# Gaussmeter_ver2.net
KiCad netlist of a schematic drawn in EAGLE
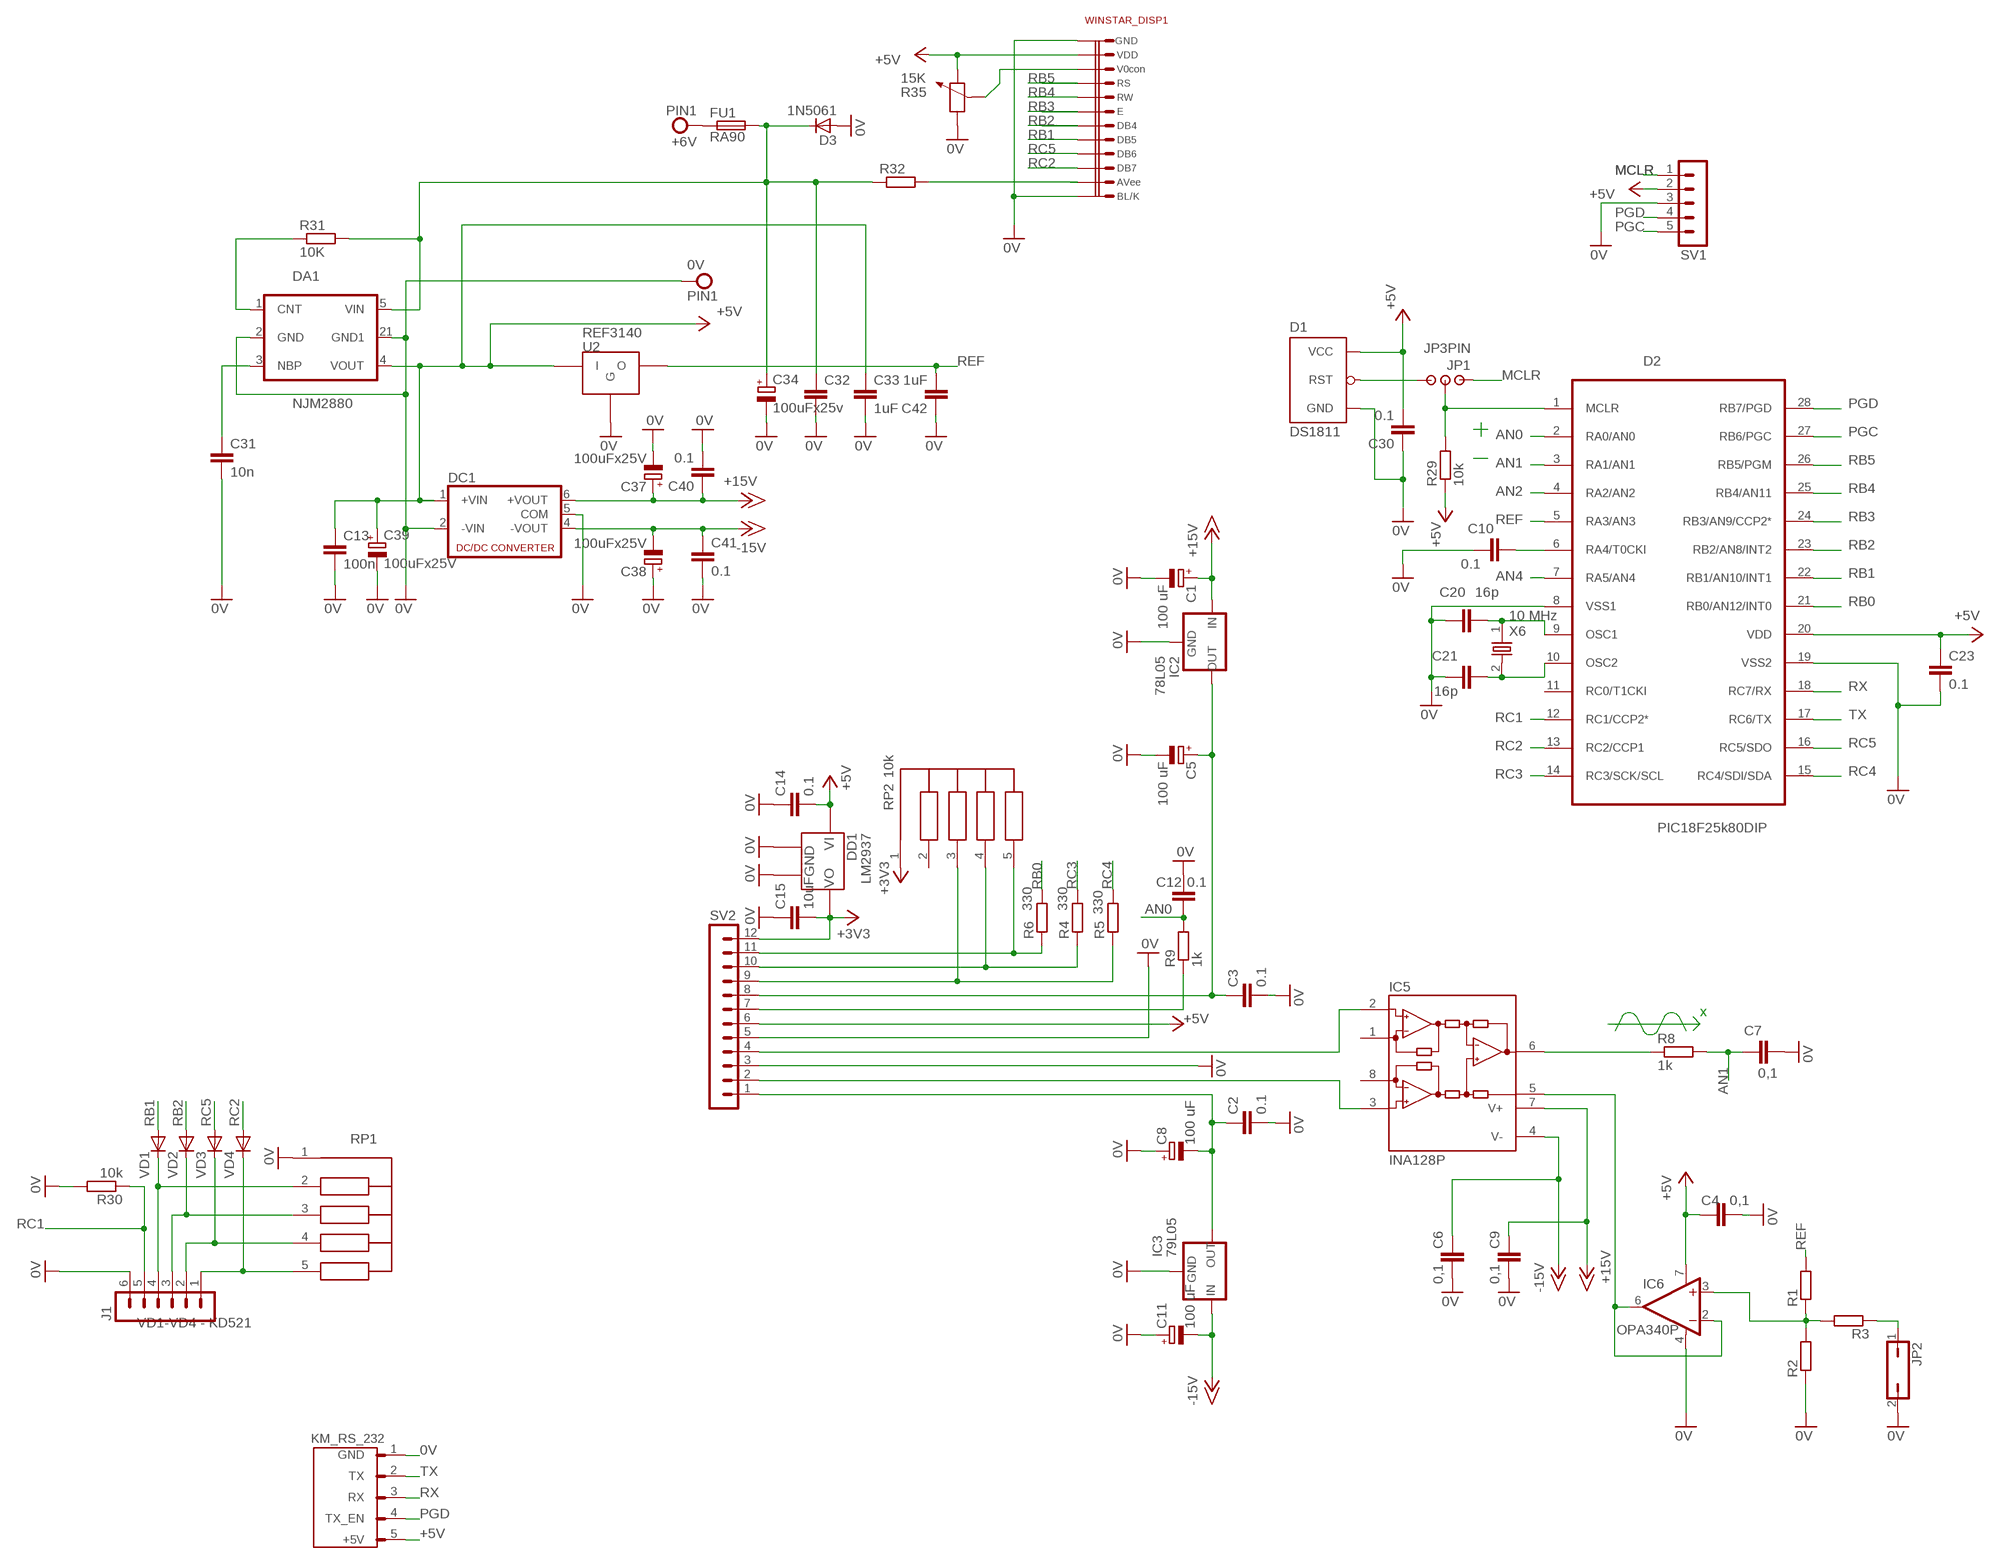
[diagram p0: schematic, sheet 1]

(export (version "E")
  (design (tool "Eeschema 10.0.6"))
  (components
    (comp (ref "+6V")
      (value "PIN1")
      (footprint "eagle-import:PIN1")
      (libsource (lib "eagle-import") (part "PIN1"))
    )
    (comp (ref "0V")
      (value "PIN1")
      (footprint "eagle-import:PIN1")
      (libsource (lib "eagle-import") (part "PIN1"))
    )
    (comp (ref "C1")
      (value "100 uF")
      (footprint "eagle-import:E2,5-6")
      (libsource (lib "eagle-import") (part "CPOL-EUE2.5-6"))
    )
    (comp (ref "C2")
      (value "0.1")
      (footprint "eagle-import:C0805")
      (libsource (lib "eagle-import") (part "C-EUC0805"))
    )
    (comp (ref "C3")
      (value "0.1")
      (footprint "eagle-import:C0805")
      (libsource (lib "eagle-import") (part "C-EUC0805"))
    )
    (comp (ref "C4")
      (value "0,1")
      (footprint "eagle-import:C0805")
      (libsource (lib "eagle-import") (part "C-EUC0805"))
    )
    (comp (ref "C5")
      (value "100 uF")
      (footprint "eagle-import:E2,5-6")
      (libsource (lib "eagle-import") (part "CPOL-EUE2.5-6"))
    )
    (comp (ref "C6")
      (value "0,1")
      (footprint "eagle-import:C0805")
      (libsource (lib "eagle-import") (part "C-EUC0805"))
    )
    (comp (ref "C7")
      (value "0,1")
      (footprint "eagle-import:C0805")
      (libsource (lib "eagle-import") (part "C-EUC0805"))
    )
    (comp (ref "C8")
      (value "100 uF")
      (footprint "eagle-import:E2,5-6")
      (libsource (lib "eagle-import") (part "CPOL-EUE2.5-6"))
    )
    (comp (ref "C9")
      (value "0,1")
      (footprint "eagle-import:C0805")
      (libsource (lib "eagle-import") (part "C-EUC0805"))
    )
    (comp (ref "C10")
      (value "0.1")
      (footprint "eagle-import:C0805D")
      (libsource (lib "eagle-import") (part "C0805"))
    )
    (comp (ref "C11")
      (value "100 uF")
      (footprint "eagle-import:E2,5-6")
      (libsource (lib "eagle-import") (part "CPOL-EUE2.5-6"))
    )
    (comp (ref "C12")
      (value "0.1")
      (footprint "eagle-import:C0805")
      (libsource (lib "eagle-import") (part "C-EUC0805"))
    )
    (comp (ref "C13")
      (value "100n")
      (footprint "eagle-import:C0805D")
      (libsource (lib "eagle-import") (part "C0805"))
    )
    (comp (ref "C14")
      (value "0.1")
      (footprint "eagle-import:C0805D")
      (libsource (lib "eagle-import") (part "C0805"))
    )
    (comp (ref "C15")
      (value "10uF")
      (footprint "eagle-import:C0805D")
      (libsource (lib "eagle-import") (part "C0805"))
    )
    (comp (ref "C20")
      (value "16p")
      (footprint "eagle-import:C0805D")
      (libsource (lib "eagle-import") (part "C0805"))
    )
    (comp (ref "C21")
      (value "16p")
      (footprint "eagle-import:C0805D")
      (libsource (lib "eagle-import") (part "C0805"))
    )
    (comp (ref "C23")
      (value "0.1")
      (footprint "eagle-import:C0805")
      (libsource (lib "eagle-import") (part "C-EUC0805"))
    )
    (comp (ref "C30")
      (value "0.1")
      (footprint "eagle-import:C0805D")
      (libsource (lib "eagle-import") (part "C0805"))
    )
    (comp (ref "C31")
      (value "10n")
      (footprint "eagle-import:C0805D")
      (libsource (lib "eagle-import") (part "C0805"))
    )
    (comp (ref "C32")
      (value "C0805")
      (footprint "eagle-import:C0805D")
      (libsource (lib "eagle-import") (part "C0805"))
    )
    (comp (ref "C33")
      (value "1uF")
      (footprint "eagle-import:C0805D")
      (libsource (lib "eagle-import") (part "C0805"))
    )
    (comp (ref "C34")
      (value "100uFx25v")
      (footprint "eagle-import:E2,5-6")
      (libsource (lib "eagle-import") (part "CPOL-EUE2.5-6"))
    )
    (comp (ref "C37")
      (value "100uFx25V")
      (footprint "eagle-import:E2,5-6")
      (libsource (lib "eagle-import") (part "CPOL-EUE2.5-6"))
    )
    (comp (ref "C38")
      (value "100uFx25V")
      (footprint "eagle-import:E2,5-6")
      (libsource (lib "eagle-import") (part "CPOL-EUE2.5-6"))
    )
    (comp (ref "C39")
      (value "100uFx25V")
      (footprint "eagle-import:E2,5-6")
      (libsource (lib "eagle-import") (part "CPOL-EUE2.5-6"))
    )
    (comp (ref "C40")
      (value "0.1")
      (footprint "eagle-import:C0805D")
      (libsource (lib "eagle-import") (part "C0805"))
    )
    (comp (ref "C41")
      (value "0.1")
      (footprint "eagle-import:C0805D")
      (libsource (lib "eagle-import") (part "C0805"))
    )
    (comp (ref "C42")
      (value "1uF")
      (footprint "eagle-import:C0805D")
      (libsource (lib "eagle-import") (part "C0805"))
    )
    (comp (ref "D1")
      (value "DS1811")
      (footprint "eagle-import:TO92-60")
      (libsource (lib "eagle-import") (part "DS1811"))
    )
    (comp (ref "D2")
      (value "PIC18F25k80DIP")
      (footprint "eagle-import:DIL28-3")
      (libsource (lib "eagle-import") (part "PIC18F2320DIP"))
    )
    (comp (ref "D3")
      (value "1N5061")
      (footprint "eagle-import:DO41-10")
      (libsource (lib "eagle-import") (part "1N5061"))
    )
    (comp (ref "DA1")
      (value "NJM2880")
      (footprint "eagle-import:SOT89-5")
      (libsource (lib "eagle-import") (part "NJM2880"))
    )
    (comp (ref "DC1")
      (value "NMA")
      (footprint "eagle-import:NMA")
      (fields (field (name "MF") "C & D TECHNOLOGIES, INC") (field (name "MPN") "NMA0515SC"))
      (libsource (lib "eagle-import") (part "NMA"))
    )
    (comp (ref "DD1")
      (value "LM2937")
      (footprint "eagle-import:SOT223")
      (libsource (lib "eagle-import") (part "LM2937"))
    )
    (comp (ref "FU1")
      (value "RA90")
      (footprint "eagle-import:RA90")
      (libsource (lib "eagle-import") (part "RA90"))
    )
    (comp (ref "IC2")
      (value "78L05")
      (footprint "eagle-import:78LXX")
      (libsource (lib "eagle-import") (part "78LXX"))
    )
    (comp (ref "IC3")
      (value "79L05")
      (footprint "eagle-import:79LXX")
      (libsource (lib "eagle-import") (part "79LXX"))
    )
    (comp (ref "IC5")
      (value "INA128P")
      (footprint "eagle-import:DIL08")
      (fields (field (name "MF") "TEXAS INSTRUMENTS"))
      (libsource (lib "eagle-import") (part "INA128P"))
    )
    (comp (ref "IC6")
      (value "OPA340P")
      (footprint "eagle-import:DIL08")
      (fields (field (name "MPN") "OPA340PA"))
      (libsource (lib "eagle-import") (part "OPA340P"))
    )
    (comp (ref "J1")
      (value "MA06-1")
      (footprint "eagle-import:MA06-1")
      (libsource (lib "eagle-import") (part "MA06-1"))
    )
    (comp (ref "JP1")
      (value "JP3PIN")
      (footprint "eagle-import:PLC-3PIN")
      (libsource (lib "eagle-import") (part "JP3PIN"))
    )
    (comp (ref "JP2")
      (value "JP1Q")
      (footprint "eagle-import:JP1")
      (libsource (lib "eagle-import") (part "JP1Q"))
    )
    (comp (ref "R1")
      (value "R-EU_R0805")
      (footprint "eagle-import:R0805")
      (libsource (lib "eagle-import") (part "R-EU_R0805"))
    )
    (comp (ref "R2")
      (value "R-EU_R0805")
      (footprint "eagle-import:R0805")
      (libsource (lib "eagle-import") (part "R-EU_R0805"))
    )
    (comp (ref "R3")
      (value "R-EU_R0805")
      (footprint "eagle-import:R0805")
      (libsource (lib "eagle-import") (part "R-EU_R0805"))
    )
    (comp (ref "R4")
      (value "330")
      (footprint "eagle-import:R0805")
      (libsource (lib "eagle-import") (part "R-EU_R0805"))
    )
    (comp (ref "R5")
      (value "330")
      (footprint "eagle-import:R0805")
      (libsource (lib "eagle-import") (part "R-EU_R0805"))
    )
    (comp (ref "R6")
      (value "330")
      (footprint "eagle-import:R0805")
      (libsource (lib "eagle-import") (part "R-EU_R0805"))
    )
    (comp (ref "R8")
      (value "1k")
      (footprint "eagle-import:R0805")
      (libsource (lib "eagle-import") (part "R-EU_R0805"))
    )
    (comp (ref "R9")
      (value "1k")
      (footprint "eagle-import:R0805")
      (libsource (lib "eagle-import") (part "R-EU_R0805"))
    )
    (comp (ref "R29")
      (value "10k")
      (footprint "eagle-import:R0805D")
      (libsource (lib "eagle-import") (part "R0805"))
    )
    (comp (ref "R30")
      (value "10k")
      (footprint "eagle-import:R0805D")
      (libsource (lib "eagle-import") (part "R0805"))
    )
    (comp (ref "R31")
      (value "10K")
      (footprint "eagle-import:R0805D")
      (libsource (lib "eagle-import") (part "R0805"))
    )
    (comp (ref "R32")
      (value "MLT025\"")
      (footprint "eagle-import:0207_10")
      (libsource (lib "eagle-import") (part "MLT025{dblquote}"))
    )
    (comp (ref "R35")
      (value "15K")
      (footprint "eagle-import:RTRIM3329H")
      (libsource (lib "eagle-import") (part "RTRIM3329H"))
    )
    (comp (ref "RP1")
      (value "NR1-4-4")
      (footprint "eagle-import:SIP5")
      (libsource (lib "eagle-import") (part "NR1-4-4"))
    )
    (comp (ref "RP2")
      (value "10k")
      (footprint "eagle-import:SIP5")
      (libsource (lib "eagle-import") (part "NR1-4-4"))
    )
    (comp (ref "SV1")
      (value "MA05-1")
      (footprint "eagle-import:MA05-1")
      (libsource (lib "eagle-import") (part "MA05-1"))
    )
    (comp (ref "SV2")
      (value "MA12-1")
      (footprint "eagle-import:MA12-1")
      (libsource (lib "eagle-import") (part "MA12-1"))
    )
    (comp (ref "U2")
      (value "REF3140")
      (footprint "eagle-import:SOT23-W")
      (libsource (lib "eagle-import") (part "REF3140"))
    )
    (comp (ref "VD1")
      (value "KD521")
      (footprint "eagle-import:DO35-10")
      (libsource (lib "eagle-import") (part "KD521"))
    )
    (comp (ref "VD2")
      (value "KD521")
      (footprint "eagle-import:DO35-10")
      (libsource (lib "eagle-import") (part "KD521"))
    )
    (comp (ref "VD3")
      (value "KD521")
      (footprint "eagle-import:DO35-10")
      (libsource (lib "eagle-import") (part "KD521"))
    )
    (comp (ref "VD4")
      (value "KD521")
      (footprint "eagle-import:DO35-10")
      (libsource (lib "eagle-import") (part "KD521"))
    )
    (comp (ref "WINSTAR_DISP1")
      (value "WINSTAR16X4DSPL_12")
      (footprint "eagle-import:WINSTAR16X4_12")
      (libsource (lib "eagle-import") (part "WINSTAR16X4DSPL_12"))
    )
    (comp (ref "X1")
      (value "KM_RS_232")
      (footprint "eagle-import:KM_RS_232")
      (libsource (lib "eagle-import") (part "KM_RS_232"))
    )
    (comp (ref "X6")
      (value "10 MHz")
      (footprint "eagle-import:HC49_S")
      (libsource (lib "eagle-import") (part "HC49/S"))
    )
  )
  (nets
    (net (code "1") (name "+3V3") (class "Default")
      (node (ref "C15") (pin "2") (pinfunction "2_2") (pintype "passive"))
      (node (ref "DD1") (pin "OUTPUT") (pinfunction "VO_OUTPUT") (pintype "power_in"))
      (node (ref "RP2") (pin "1") (pinfunction "P$1_1") (pintype "passive"))
      (node (ref "SV2") (pin "12") (pinfunction "12_12") (pintype "passive"))
    )
    (net (code "2") (name "+5V") (class "Default")
      (node (ref "C13") (pin "1") (pinfunction "1_1") (pintype "passive"))
      (node (ref "C14") (pin "2") (pinfunction "2_2") (pintype "passive"))
      (node (ref "C23") (pin "1") (pinfunction "1_1") (pintype "passive"))
      (node (ref "C30") (pin "2") (pinfunction "2_2") (pintype "passive"))
      (node (ref "C33") (pin "1") (pinfunction "1_1") (pintype "passive"))
      (node (ref "C39") (pin "+") (pinfunction "+_+") (pintype "passive"))
      (node (ref "C4") (pin "2") (pinfunction "2_2") (pintype "passive"))
      (node (ref "D1") (pin "2") (pinfunction "VCC_2") (pintype "power_in"))
      (node (ref "D2") (pin "20") (pinfunction "VDD_20") (pintype "bidirectional"))
      (node (ref "DA1") (pin "4") (pinfunction "VOUT_4") (pintype "bidirectional"))
      (node (ref "DC1") (pin "1") (pinfunction "+VIN_1") (pintype "passive"))
      (node (ref "DD1") (pin "INPUT") (pinfunction "VI_INPUT") (pintype "power_in"))
      (node (ref "IC6") (pin "7") (pinfunction "V+_7") (pintype "power_in"))
      (node (ref "R29") (pin "P$1") (pinfunction "1_P$1") (pintype "passive"))
      (node (ref "R35") (pin "2") (pinfunction "2_2") (pintype "passive"))
      (node (ref "SV1") (pin "2") (pinfunction "2_2") (pintype "passive"))
      (node (ref "SV2") (pin "6") (pinfunction "6_6") (pintype "passive"))
      (node (ref "U2") (pin "IN") (pinfunction "I_IN") (pintype "bidirectional"))
      (node (ref "WINSTAR_DISP1") (pin "P$2") (pinfunction "VDD_P$2") (pintype "bidirectional"))
      (node (ref "X1") (pin "5") (pinfunction "+5V_5") (pintype "bidirectional"))
    )
    (net (code "3") (name "+15V") (class "Default")
      (node (ref "C1") (pin "+") (pinfunction "+_+") (pintype "passive"))
      (node (ref "C37") (pin "+") (pinfunction "+_+") (pintype "passive"))
      (node (ref "C40") (pin "1") (pinfunction "1_1") (pintype "passive"))
      (node (ref "C9") (pin "1") (pinfunction "1_1") (pintype "passive"))
      (node (ref "DC1") (pin "6") (pinfunction "+VOUT_6") (pintype "passive"))
      (node (ref "IC2") (pin "IN") (pinfunction "IN_IN") (pintype "input"))
      (node (ref "IC5") (pin "7") (pinfunction "V+_7") (pintype "power_in"))
    )
    (net (code "4") (name "-15V") (class "Default")
      (node (ref "C11") (pin "-") (pinfunction "-_-") (pintype "passive"))
      (node (ref "C38") (pin "-") (pinfunction "-_-") (pintype "passive"))
      (node (ref "C41") (pin "1") (pinfunction "1_1") (pintype "passive"))
      (node (ref "C6") (pin "1") (pinfunction "1_1") (pintype "passive"))
      (node (ref "DC1") (pin "4") (pinfunction "-VOUT_4") (pintype "passive"))
      (node (ref "IC3") (pin "IN") (pinfunction "IN_IN") (pintype "input"))
      (node (ref "IC5") (pin "4") (pinfunction "V-_4") (pintype "power_in"))
    )
    (net (code "5") (name "/AN0") (class "Default")
      (node (ref "C12") (pin "1") (pinfunction "1_1") (pintype "passive"))
      (node (ref "D2") (pin "2") (pinfunction "RA0/AN0_2") (pintype "bidirectional"))
      (node (ref "R9") (pin "2") (pinfunction "2_2") (pintype "passive"))
    )
    (net (code "6") (name "/AN1") (class "Default")
      (node (ref "C7") (pin "1") (pinfunction "1_1") (pintype "passive"))
      (node (ref "D2") (pin "3") (pinfunction "RA1/AN1_3") (pintype "bidirectional"))
      (node (ref "R8") (pin "2") (pinfunction "2_2") (pintype "passive"))
    )
    (net (code "7") (name "/AN2") (class "Default")
      (node (ref "D2") (pin "4") (pinfunction "RA2/AN2_4") (pintype "bidirectional"))
    )
    (net (code "8") (name "/AN4") (class "Default")
      (node (ref "D2") (pin "7") (pinfunction "RA5/AN4_7") (pintype "bidirectional"))
    )
    (net (code "9") (name "/MCLR") (class "Default")
      (node (ref "JP1") (pin "P$1") (pinfunction "P$1_P$1") (pintype "bidirectional"))
      (node (ref "SV1") (pin "1") (pinfunction "1_1") (pintype "passive"))
    )
    (net (code "10") (name "/PGC") (class "Default")
      (node (ref "D2") (pin "27") (pinfunction "RB6/PGC_27") (pintype "bidirectional"))
      (node (ref "SV1") (pin "5") (pinfunction "5_5") (pintype "passive"))
    )
    (net (code "11") (name "/PGD") (class "Default")
      (node (ref "D2") (pin "28") (pinfunction "RB7/PGD_28") (pintype "bidirectional"))
      (node (ref "SV1") (pin "4") (pinfunction "4_4") (pintype "passive"))
      (node (ref "X1") (pin "4") (pinfunction "TX_EN_4") (pintype "bidirectional"))
    )
    (net (code "12") (name "/RB0") (class "Default")
      (node (ref "D2") (pin "21") (pinfunction "RB0/AN12/INT0_21") (pintype "bidirectional"))
      (node (ref "R6") (pin "2") (pinfunction "2_2") (pintype "passive"))
    )
    (net (code "13") (name "/RB1") (class "Default")
      (node (ref "D2") (pin "22") (pinfunction "RB1/AN10/INT1_22") (pintype "bidirectional"))
      (node (ref "VD1") (pin "A") (pinfunction "A_A") (pintype "passive"))
      (node (ref "WINSTAR_DISP1") (pin "P$8") (pinfunction "DB5_P$8") (pintype "bidirectional"))
    )
    (net (code "14") (name "/RB2") (class "Default")
      (node (ref "D2") (pin "23") (pinfunction "RB2/AN8/INT2_23") (pintype "bidirectional"))
      (node (ref "VD2") (pin "A") (pinfunction "A_A") (pintype "passive"))
      (node (ref "WINSTAR_DISP1") (pin "P$7") (pinfunction "DB4_P$7") (pintype "bidirectional"))
    )
    (net (code "15") (name "/RB3") (class "Default")
      (node (ref "D2") (pin "24") (pinfunction "RB3/AN9/CCP2*_24") (pintype "bidirectional"))
      (node (ref "WINSTAR_DISP1") (pin "P$6") (pinfunction "E_P$6") (pintype "bidirectional"))
    )
    (net (code "16") (name "/RB4") (class "Default")
      (node (ref "D2") (pin "25") (pinfunction "RB4/AN11_25") (pintype "bidirectional"))
      (node (ref "WINSTAR_DISP1") (pin "P$5") (pinfunction "RW_P$5") (pintype "bidirectional"))
    )
    (net (code "17") (name "/RB5") (class "Default")
      (node (ref "D2") (pin "26") (pinfunction "RB5/PGM_26") (pintype "bidirectional"))
      (node (ref "WINSTAR_DISP1") (pin "P$4") (pinfunction "RS_P$4") (pintype "bidirectional"))
    )
    (net (code "18") (name "/RC1") (class "Default")
      (node (ref "D2") (pin "12") (pinfunction "RC1/CCP2*_12") (pintype "bidirectional"))
      (node (ref "J1") (pin "5") (pinfunction "5_5") (pintype "passive"))
      (node (ref "R30") (pin "P$1") (pinfunction "1_P$1") (pintype "passive"))
    )
    (net (code "19") (name "/RC2") (class "Default")
      (node (ref "D2") (pin "13") (pinfunction "RC2/CCP1_13") (pintype "bidirectional"))
      (node (ref "VD4") (pin "A") (pinfunction "A_A") (pintype "passive"))
      (node (ref "WINSTAR_DISP1") (pin "P$10") (pinfunction "DB7_P$10") (pintype "bidirectional"))
    )
    (net (code "20") (name "/RC3") (class "Default")
      (node (ref "D2") (pin "14") (pinfunction "RC3/SCK/SCL_14") (pintype "bidirectional"))
      (node (ref "R4") (pin "2") (pinfunction "2_2") (pintype "passive"))
    )
    (net (code "21") (name "/RC4") (class "Default")
      (node (ref "D2") (pin "15") (pinfunction "RC4/SDI/SDA_15") (pintype "bidirectional"))
      (node (ref "R5") (pin "2") (pinfunction "2_2") (pintype "passive"))
    )
    (net (code "22") (name "/RC5") (class "Default")
      (node (ref "D2") (pin "16") (pinfunction "RC5/SDO_16") (pintype "bidirectional"))
      (node (ref "VD3") (pin "A") (pinfunction "A_A") (pintype "passive"))
      (node (ref "WINSTAR_DISP1") (pin "P$9") (pinfunction "DB6_P$9") (pintype "bidirectional"))
    )
    (net (code "23") (name "/REF") (class "Default")
      (node (ref "C42") (pin "2") (pinfunction "2_2") (pintype "passive"))
      (node (ref "D2") (pin "5") (pinfunction "RA3/AN3_5") (pintype "bidirectional"))
      (node (ref "R1") (pin "2") (pinfunction "2_2") (pintype "passive"))
      (node (ref "U2") (pin "OUT") (pinfunction "O_OUT") (pintype "bidirectional"))
    )
    (net (code "24") (name "/RX") (class "Default")
      (node (ref "D2") (pin "18") (pinfunction "RC7/RX_18") (pintype "bidirectional"))
      (node (ref "X1") (pin "3") (pinfunction "RX_3") (pintype "bidirectional"))
    )
    (net (code "25") (name "/TX") (class "Default")
      (node (ref "D2") (pin "17") (pinfunction "RC6/TX_17") (pintype "bidirectional"))
      (node (ref "X1") (pin "2") (pinfunction "TX_2") (pintype "bidirectional"))
    )
    (net (code "26") (name "0V") (class "Default")
      (node (ref "0V") (pin "P$1") (pinfunction "P$1_P$1") (pintype "passive"))
      (node (ref "C1") (pin "-") (pinfunction "-_-") (pintype "passive"))
      (node (ref "C10") (pin "2") (pinfunction "2_2") (pintype "passive"))
      (node (ref "C11") (pin "+") (pinfunction "+_+") (pintype "passive"))
      (node (ref "C12") (pin "2") (pinfunction "2_2") (pintype "passive"))
      (node (ref "C13") (pin "2") (pinfunction "2_2") (pintype "passive"))
      (node (ref "C14") (pin "1") (pinfunction "1_1") (pintype "passive"))
      (node (ref "C15") (pin "1") (pinfunction "1_1") (pintype "passive"))
      (node (ref "C2") (pin "2") (pinfunction "2_2") (pintype "passive"))
      (node (ref "C20") (pin "2") (pinfunction "2_2") (pintype "passive"))
      (node (ref "C21") (pin "1") (pinfunction "1_1") (pintype "passive"))
      (node (ref "C23") (pin "2") (pinfunction "2_2") (pintype "passive"))
      (node (ref "C3") (pin "2") (pinfunction "2_2") (pintype "passive"))
      (node (ref "C30") (pin "1") (pinfunction "1_1") (pintype "passive"))
      (node (ref "C31") (pin "2") (pinfunction "2_2") (pintype "passive"))
      (node (ref "C32") (pin "2") (pinfunction "2_2") (pintype "passive"))
      (node (ref "C33") (pin "2") (pinfunction "2_2") (pintype "passive"))
      (node (ref "C34") (pin "-") (pinfunction "-_-") (pintype "passive"))
      (node (ref "C37") (pin "-") (pinfunction "-_-") (pintype "passive"))
      (node (ref "C38") (pin "+") (pinfunction "+_+") (pintype "passive"))
      (node (ref "C39") (pin "-") (pinfunction "-_-") (pintype "passive"))
      (node (ref "C4") (pin "1") (pinfunction "1_1") (pintype "passive"))
      (node (ref "C40") (pin "2") (pinfunction "2_2") (pintype "passive"))
      (node (ref "C41") (pin "2") (pinfunction "2_2") (pintype "passive"))
      (node (ref "C42") (pin "1") (pinfunction "1_1") (pintype "passive"))
      (node (ref "C5") (pin "-") (pinfunction "-_-") (pintype "passive"))
      (node (ref "C6") (pin "2") (pinfunction "2_2") (pintype "passive"))
      (node (ref "C7") (pin "2") (pinfunction "2_2") (pintype "passive"))
      (node (ref "C8") (pin "+") (pinfunction "+_+") (pintype "passive"))
      (node (ref "C9") (pin "2") (pinfunction "2_2") (pintype "passive"))
      (node (ref "D1") (pin "3") (pinfunction "GND_3") (pintype "power_in"))
      (node (ref "D2") (pin "19") (pinfunction "VSS2_19") (pintype "bidirectional"))
      (node (ref "D2") (pin "8") (pinfunction "VSS1_8") (pintype "bidirectional"))
      (node (ref "D3") (pin "A") (pinfunction "A_A") (pintype "passive"))
      (node (ref "DA1") (pin "2") (pinfunction "GND_2") (pintype "bidirectional"))
      (node (ref "DA1") (pin "21") (pinfunction "GND1_21") (pintype "bidirectional"))
      (node (ref "DC1") (pin "2") (pinfunction "-VIN_2") (pintype "passive"))
      (node (ref "DC1") (pin "5") (pinfunction "COM_5") (pintype "passive"))
      (node (ref "DD1") (pin "GND") (pinfunction "GND_GND") (pintype "power_in"))
      (node (ref "DD1") (pin "GND@1") (pinfunction "GND_GND@1") (pintype "power_in"))
      (node (ref "IC2") (pin "GND") (pinfunction "GND_GND") (pintype "input"))
      (node (ref "IC3") (pin "GND") (pinfunction "GND_GND") (pintype "input"))
      (node (ref "IC6") (pin "4") (pinfunction "V-_4") (pintype "power_in"))
      (node (ref "J1") (pin "6") (pinfunction "6_6") (pintype "passive"))
      (node (ref "JP2") (pin "2") (pinfunction "2_2") (pintype "passive"))
      (node (ref "R2") (pin "1") (pinfunction "1_1") (pintype "passive"))
      (node (ref "R30") (pin "P$2") (pinfunction "2_P$2") (pintype "passive"))
      (node (ref "R35") (pin "1") (pinfunction "1_1") (pintype "passive"))
      (node (ref "RP1") (pin "1") (pinfunction "P$1_1") (pintype "passive"))
      (node (ref "SV1") (pin "3") (pinfunction "3_3") (pintype "passive"))
      (node (ref "SV2") (pin "3") (pinfunction "3_3") (pintype "passive"))
      (node (ref "SV2") (pin "5") (pinfunction "5_5") (pintype "passive"))
      (node (ref "U2") (pin "GND") (pinfunction "G_GND") (pintype "bidirectional"))
      (node (ref "WINSTAR_DISP1") (pin "P$1") (pinfunction "GND_P$1") (pintype "bidirectional"))
      (node (ref "WINSTAR_DISP1") (pin "P$12") (pinfunction "KB/L_P$12") (pintype "bidirectional"))
      (node (ref "X1") (pin "1") (pinfunction "GND_1") (pintype "bidirectional"))
    )
    (net (code "27") (name "Net-(C2-Pad1)") (class "Default")
      (node (ref "C2") (pin "1") (pinfunction "1_1") (pintype "passive"))
      (node (ref "C8") (pin "-") (pinfunction "-_-") (pintype "passive"))
      (node (ref "IC3") (pin "OUT") (pinfunction "OUT_OUT") (pintype "passive"))
      (node (ref "SV2") (pin "1") (pinfunction "1_1") (pintype "passive"))
    )
    (net (code "28") (name "Net-(C3-Pad1)") (class "Default")
      (node (ref "C3") (pin "1") (pinfunction "1_1") (pintype "passive"))
      (node (ref "C5") (pin "+") (pinfunction "+_+") (pintype "passive"))
      (node (ref "IC2") (pin "OUT") (pinfunction "OUT_OUT") (pintype "passive"))
      (node (ref "SV2") (pin "8") (pinfunction "8_8") (pintype "passive"))
    )
    (net (code "29") (name "Net-(D1-RST)") (class "Default")
      (node (ref "D1") (pin "1") (pinfunction "RST_1") (pintype "output"))
      (node (ref "JP1") (pin "P$3") (pinfunction "P$3_P$3") (pintype "bidirectional"))
    )
    (net (code "30") (name "Net-(D2-MCLR)") (class "Default")
      (node (ref "D2") (pin "1") (pinfunction "MCLR_1") (pintype "bidirectional"))
      (node (ref "JP1") (pin "P$2") (pinfunction "P$2_P$2") (pintype "bidirectional"))
      (node (ref "R29") (pin "P$2") (pinfunction "2_P$2") (pintype "passive"))
    )
    (net (code "31") (name "Net-(D2-OSC1)") (class "Default")
      (node (ref "C20") (pin "1") (pinfunction "1_1") (pintype "passive"))
      (node (ref "D2") (pin "9") (pinfunction "OSC1_9") (pintype "bidirectional"))
      (node (ref "X6") (pin "1") (pinfunction "1_1") (pintype "passive"))
    )
    (net (code "32") (name "Net-(D2-OSC2)") (class "Default")
      (node (ref "C21") (pin "2") (pinfunction "2_2") (pintype "passive"))
      (node (ref "D2") (pin "10") (pinfunction "OSC2_10") (pintype "bidirectional"))
      (node (ref "X6") (pin "2") (pinfunction "2_2") (pintype "passive"))
    )
    (net (code "33") (name "Net-(D2-RA4{slash}T0CKI)") (class "Default")
      (node (ref "C10") (pin "1") (pinfunction "1_1") (pintype "passive"))
      (node (ref "D2") (pin "6") (pinfunction "RA4/T0CKI_6") (pintype "bidirectional"))
    )
    (net (code "34") (name "Net-(DA1-CNT)") (class "Default")
      (node (ref "DA1") (pin "1") (pinfunction "CNT_1") (pintype "bidirectional"))
      (node (ref "R31") (pin "P$1") (pinfunction "1_P$1") (pintype "passive"))
    )
    (net (code "35") (name "Net-(DA1-NBP)") (class "Default")
      (node (ref "C31") (pin "1") (pinfunction "1_1") (pintype "passive"))
      (node (ref "DA1") (pin "3") (pinfunction "NBP_3") (pintype "bidirectional"))
    )
    (net (code "36") (name "Net-(DA1-VIN)") (class "Default")
      (node (ref "C32") (pin "1") (pinfunction "1_1") (pintype "passive"))
      (node (ref "C34") (pin "+") (pinfunction "+_+") (pintype "passive"))
      (node (ref "D3") (pin "C") (pinfunction "C_C") (pintype "passive"))
      (node (ref "DA1") (pin "5") (pinfunction "VIN_5") (pintype "bidirectional"))
      (node (ref "FU1") (pin "P$2") (pinfunction "2_P$2") (pintype "passive"))
      (node (ref "R31") (pin "P$2") (pinfunction "2_P$2") (pintype "passive"))
      (node (ref "R32") (pin "1") (pinfunction "1_1") (pintype "passive"))
    )
    (net (code "37") (name "Net-(FU1-1)") (class "Default")
      (node (ref "+6V") (pin "P$1") (pinfunction "P$1_P$1") (pintype "passive"))
      (node (ref "FU1") (pin "P$1") (pinfunction "1_P$1") (pintype "passive"))
    )
    (net (code "38") (name "Net-(IC5-+IN)") (class "Default")
      (node (ref "IC5") (pin "3") (pinfunction "+IN_3") (pintype "input"))
      (node (ref "SV2") (pin "2") (pinfunction "2_2") (pintype "passive"))
    )
    (net (code "39") (name "Net-(IC5--IN)") (class "Default")
      (node (ref "IC5") (pin "2") (pinfunction "-IN_2") (pintype "input"))
      (node (ref "SV2") (pin "4") (pinfunction "4_4") (pintype "passive"))
    )
    (net (code "40") (name "Net-(IC5-OUT)") (class "Default")
      (node (ref "IC5") (pin "6") (pinfunction "OUT_6") (pintype "output"))
      (node (ref "R8") (pin "1") (pinfunction "1_1") (pintype "passive"))
    )
    (net (code "41") (name "Net-(IC5-REF)") (class "Default")
      (node (ref "IC5") (pin "5") (pinfunction "REF_5") (pintype "passive"))
      (node (ref "IC6") (pin "2") (pinfunction "-IN_2") (pintype "input"))
      (node (ref "IC6") (pin "6") (pinfunction "OUT_6") (pintype "output"))
    )
    (net (code "42") (name "Net-(IC6-+IN)") (class "Default")
      (node (ref "IC6") (pin "3") (pinfunction "+IN_3") (pintype "input"))
      (node (ref "R1") (pin "1") (pinfunction "1_1") (pintype "passive"))
      (node (ref "R2") (pin "2") (pinfunction "2_2") (pintype "passive"))
      (node (ref "R3") (pin "2") (pinfunction "2_2") (pintype "passive"))
    )
    (net (code "43") (name "Net-(JP2-Pad1)") (class "Default")
      (node (ref "JP2") (pin "1") (pinfunction "1_1") (pintype "passive"))
      (node (ref "R3") (pin "1") (pinfunction "1_1") (pintype "passive"))
    )
    (net (code "44") (name "Net-(R9-Pad1)") (class "Default")
      (node (ref "R9") (pin "1") (pinfunction "1_1") (pintype "passive"))
      (node (ref "SV2") (pin "7") (pinfunction "7_7") (pintype "passive"))
    )
    (net (code "45") (name "Net-(RP1-P$2)") (class "Default")
      (node (ref "J1") (pin "4") (pinfunction "4_4") (pintype "passive"))
      (node (ref "RP1") (pin "2") (pinfunction "P$2_2") (pintype "passive"))
      (node (ref "VD1") (pin "C") (pinfunction "C_C") (pintype "passive"))
    )
    (net (code "46") (name "Net-(RP1-P$3)") (class "Default")
      (node (ref "J1") (pin "3") (pinfunction "3_3") (pintype "passive"))
      (node (ref "RP1") (pin "3") (pinfunction "P$3_3") (pintype "passive"))
      (node (ref "VD2") (pin "C") (pinfunction "C_C") (pintype "passive"))
    )
    (net (code "47") (name "Net-(RP1-P$4)") (class "Default")
      (node (ref "J1") (pin "2") (pinfunction "2_2") (pintype "passive"))
      (node (ref "RP1") (pin "4") (pinfunction "P$4_4") (pintype "passive"))
      (node (ref "VD3") (pin "C") (pinfunction "C_C") (pintype "passive"))
    )
    (net (code "48") (name "Net-(RP1-P$5)") (class "Default")
      (node (ref "J1") (pin "1") (pinfunction "1_1") (pintype "passive"))
      (node (ref "RP1") (pin "5") (pinfunction "P$5_5") (pintype "passive"))
      (node (ref "VD4") (pin "C") (pinfunction "C_C") (pintype "passive"))
    )
    (net (code "49") (name "Net-(RP2-P$3)") (class "Default")
      (node (ref "R5") (pin "1") (pinfunction "1_1") (pintype "passive"))
      (node (ref "RP2") (pin "3") (pinfunction "P$3_3") (pintype "passive"))
      (node (ref "SV2") (pin "9") (pinfunction "9_9") (pintype "passive"))
    )
    (net (code "50") (name "Net-(RP2-P$4)") (class "Default")
      (node (ref "R4") (pin "1") (pinfunction "1_1") (pintype "passive"))
      (node (ref "RP2") (pin "4") (pinfunction "P$4_4") (pintype "passive"))
      (node (ref "SV2") (pin "10") (pinfunction "10_10") (pintype "passive"))
    )
    (net (code "51") (name "Net-(RP2-P$5)") (class "Default")
      (node (ref "R6") (pin "1") (pinfunction "1_1") (pintype "passive"))
      (node (ref "RP2") (pin "5") (pinfunction "P$5_5") (pintype "passive"))
      (node (ref "SV2") (pin "11") (pinfunction "11_11") (pintype "passive"))
    )
    (net (code "52") (name "Net-(WINSTAR_DISP1-AVEE)") (class "Default")
      (node (ref "R32") (pin "2") (pinfunction "2_2") (pintype "passive"))
      (node (ref "WINSTAR_DISP1") (pin "P$11") (pinfunction "AVEE_P$11") (pintype "bidirectional"))
    )
    (net (code "53") (name "Net-(WINSTAR_DISP1-V0CON)") (class "Default")
      (node (ref "R35") (pin "3") (pinfunction "3_3") (pintype "passive"))
      (node (ref "WINSTAR_DISP1") (pin "P$3") (pinfunction "V0CON_P$3") (pintype "bidirectional"))
    )
    (net (code "54") (name "unconnected-(D2-RC0{slash}T1CKI-Pad11)") (class "Default")
      (node (ref "D2") (pin "11") (pinfunction "RC0/T1CKI_11") (pintype "bidirectional"))
    )
    (net (code "55") (name "unconnected-(IC5-RG-Pad1)") (class "Default")
      (node (ref "IC5") (pin "1") (pinfunction "RG_1") (pintype "passive"))
    )
    (net (code "56") (name "unconnected-(IC5-RG-Pad8)") (class "Default")
      (node (ref "IC5") (pin "8") (pinfunction "RG_8") (pintype "passive"))
    )
    (net (code "57") (name "unconnected-(RP2-P$2-Pad2)") (class "Default")
      (node (ref "RP2") (pin "2") (pinfunction "P$2_2") (pintype "passive"))
    )
  )
)
